# Adafruit_QT2040_Trinkey.net
KiCad netlist of a schematic drawn in EAGLE
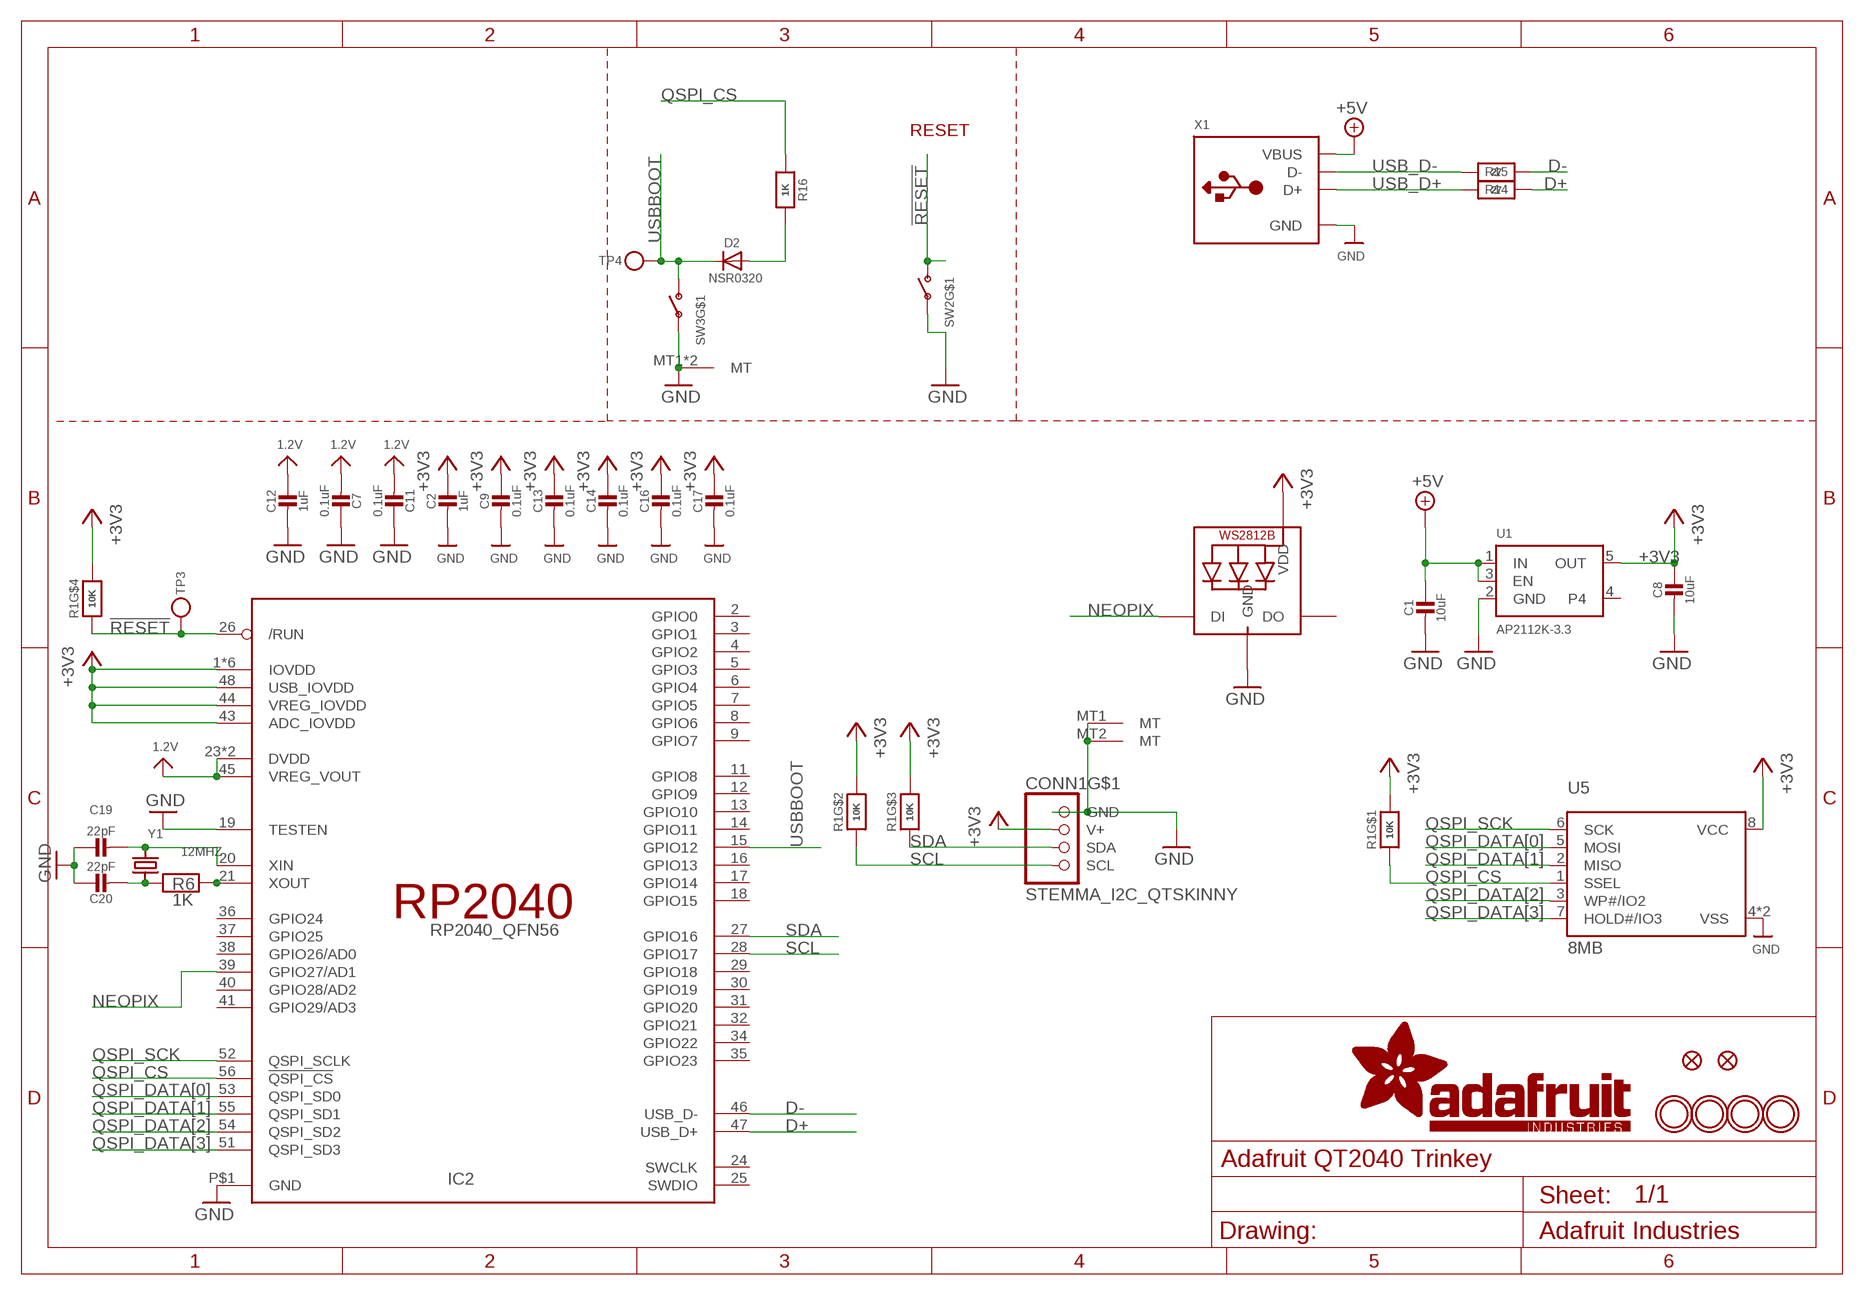
[diagram p0: schematic, sheet 1]

(export (version "E")
  (design (tool "Eeschema 10.0.6"))
  (components
    (comp (ref "C1")
      (value "10uF")
      (footprint "eagle-import:0805-NO")
      (libsource (lib "eagle-import") (part "CAP_CERAMIC0805-NOOUTLINE"))
    )
    (comp (ref "C2")
      (value "1uF")
      (footprint "eagle-import:0603-NO")
      (libsource (lib "eagle-import") (part "CAP_CERAMIC0603_NO"))
    )
    (comp (ref "C7")
      (value "0.1uF")
      (footprint "eagle-import:_0603MP")
      (libsource (lib "eagle-import") (part "CAP_CERAMIC_0603MP"))
    )
    (comp (ref "C8")
      (value "10uF")
      (footprint "eagle-import:0805-NO")
      (libsource (lib "eagle-import") (part "CAP_CERAMIC0805-NOOUTLINE"))
    )
    (comp (ref "C9")
      (value "0.1uF")
      (footprint "eagle-import:0603-NO")
      (libsource (lib "eagle-import") (part "CAP_CERAMIC0603_NO"))
    )
    (comp (ref "C11")
      (value "0.1uF")
      (footprint "eagle-import:0603-NO")
      (libsource (lib "eagle-import") (part "CAP_CERAMIC0603_NO"))
    )
    (comp (ref "C12")
      (value "1uF")
      (footprint "eagle-import:0603-NO")
      (libsource (lib "eagle-import") (part "CAP_CERAMIC0603_NO"))
    )
    (comp (ref "C13")
      (value "0.1uF")
      (footprint "eagle-import:0603-NO")
      (libsource (lib "eagle-import") (part "CAP_CERAMIC0603_NO"))
    )
    (comp (ref "C14")
      (value "0.1uF")
      (footprint "eagle-import:0603-NO")
      (libsource (lib "eagle-import") (part "CAP_CERAMIC0603_NO"))
    )
    (comp (ref "C16")
      (value "0.1uF")
      (footprint "eagle-import:0603-NO")
      (libsource (lib "eagle-import") (part "CAP_CERAMIC0603_NO"))
    )
    (comp (ref "C17")
      (value "0.1uF")
      (footprint "eagle-import:0603-NO")
      (libsource (lib "eagle-import") (part "CAP_CERAMIC0603_NO"))
    )
    (comp (ref "C19")
      (value "22pF")
      (footprint "eagle-import:0603-NO")
      (libsource (lib "eagle-import") (part "CAP_CERAMIC0603_NO"))
    )
    (comp (ref "C20")
      (value "22pF")
      (footprint "eagle-import:0603-NO")
      (libsource (lib "eagle-import") (part "CAP_CERAMIC0603_NO"))
    )
    (comp (ref "CONN1")
      (value "STEMMA_I2C_QTSKINNY")
      (footprint "eagle-import:JST_SH4_SKINNY")
      (libsource (lib "eagle-import") (part "STEMMA_I2C_QTSKINNY"))
    )
    (comp (ref "D2")
      (value "NSR0320")
      (footprint "eagle-import:SOD-323_MINI")
      (libsource (lib "eagle-import") (part "DIODE_SOD323MINI"))
    )
    (comp (ref "IC2")
      (value "RP2040_QFN56")
      (footprint "eagle-import:QFN56_7MM_REDUCEDEPAD")
      (libsource (lib "eagle-import") (part "RP2040_QFN56"))
    )
    (comp (ref "LED1")
      (value "WS2812B_SK6805_1515")
      (footprint "eagle-import:SK6805_1515")
      (libsource (lib "eagle-import") (part "WS2812B_SK6805_1515"))
    )
    (comp (ref "R1")
      (value "10K")
      (footprint "eagle-import:RESPACK_4X0603")
      (libsource (lib "eagle-import") (part "RESISTOR_4PACK"))
    )
    (comp (ref "R6")
      (value "1K")
      (footprint "eagle-import:0603-NO")
      (libsource (lib "eagle-import") (part "RESISTOR_0603_NOOUT"))
    )
    (comp (ref "R14")
      (value "27")
      (footprint "eagle-import:0603-NO")
      (libsource (lib "eagle-import") (part "RESISTOR_0603_NOOUT"))
    )
    (comp (ref "R15")
      (value "27")
      (footprint "eagle-import:0603-NO")
      (libsource (lib "eagle-import") (part "RESISTOR_0603_NOOUT"))
    )
    (comp (ref "R16")
      (value "1K")
      (footprint "eagle-import:0603-NO")
      (libsource (lib "eagle-import") (part "RESISTOR_0603_NOOUT"))
    )
    (comp (ref "SW2")
      (value "SWITCH_SPST_TACT_RA")
      (footprint "eagle-import:SPST_TACTILE_RA")
      (libsource (lib "eagle-import") (part "SWITCH_SPST_TACT_RA"))
    )
    (comp (ref "SW3")
      (value "SWITCH_SPST_TACT_RA")
      (footprint "eagle-import:SPST_TACTILE_RA")
      (libsource (lib "eagle-import") (part "SWITCH_SPST_TACT_RA"))
    )
    (comp (ref "TP3")
      (value "TESTPOINTROUND1.5MMNO")
      (footprint "eagle-import:TESTPOINT_ROUND_1.5MM_NO")
      (libsource (lib "eagle-import") (part "TESTPOINTROUND1.5MMNO"))
    )
    (comp (ref "TP4")
      (value "TESTPOINTROUND1.5MMNO")
      (footprint "eagle-import:TESTPOINT_ROUND_1.5MM_NO")
      (libsource (lib "eagle-import") (part "TESTPOINTROUND1.5MMNO"))
    )
    (comp (ref "U$1")
      (value "MOUNTINGHOLE2.5")
      (footprint "eagle-import:MOUNTINGHOLE_2.5_PLATED")
      (libsource (lib "eagle-import") (part "MOUNTINGHOLE2.5"))
    )
    (comp (ref "U$2")
      (value "MOUNTINGHOLE2.5")
      (footprint "eagle-import:MOUNTINGHOLE_2.5_PLATED")
      (libsource (lib "eagle-import") (part "MOUNTINGHOLE2.5"))
    )
    (comp (ref "U$4")
      (value "MOUNTINGHOLE2.5")
      (footprint "eagle-import:MOUNTINGHOLE_2.5_PLATED")
      (libsource (lib "eagle-import") (part "MOUNTINGHOLE2.5"))
    )
    (comp (ref "U$5")
      (value "MOUNTINGHOLE2.5")
      (footprint "eagle-import:MOUNTINGHOLE_2.5_PLATED")
      (libsource (lib "eagle-import") (part "MOUNTINGHOLE2.5"))
    )
    (comp (ref "U$6")
      (value "FIDUCIAL_1MM")
      (footprint "eagle-import:FIDUCIAL_1MM")
      (libsource (lib "eagle-import") (part "FIDUCIAL_1MM"))
    )
    (comp (ref "U$8")
      (value "FIDUCIAL_1MM")
      (footprint "eagle-import:FIDUCIAL_1MM")
      (libsource (lib "eagle-import") (part "FIDUCIAL_1MM"))
    )
    (comp (ref "U1")
      (value "AP2112K-3.3")
      (footprint "eagle-import:SOT23-5")
      (libsource (lib "eagle-import") (part "VREG_SOT23-5"))
    )
    (comp (ref "U5")
      (value "8MB")
      (footprint "eagle-import:USON8_4X4")
      (libsource (lib "eagle-import") (part "SPIFLASH_8PIN_4X4"))
    )
    (comp (ref "X1")
      (value "USB_TYPEAPCB")
      (footprint "eagle-import:USBA_PCB")
      (libsource (lib "eagle-import") (part "USB_TYPEAPCB"))
    )
    (comp (ref "Y1")
      (value "12MHZ")
      (footprint "eagle-import:CRYSTAL_2.5X2")
      (libsource (lib "eagle-import") (part "CRYSTAL2.5X2.0"))
    )
  )
  (nets
    (net (code "1") (name "+3V3") (class "Default")
      (node (ref "C13") (pin "1") (pinfunction "1_1") (pintype "passive"))
      (node (ref "C14") (pin "1") (pinfunction "1_1") (pintype "passive"))
      (node (ref "C16") (pin "1") (pinfunction "1_1") (pintype "passive"))
      (node (ref "C17") (pin "1") (pinfunction "1_1") (pintype "passive"))
      (node (ref "C2") (pin "1") (pinfunction "1_1") (pintype "passive"))
      (node (ref "C8") (pin "1") (pinfunction "1_1") (pintype "passive"))
      (node (ref "C9") (pin "1") (pinfunction "1_1") (pintype "passive"))
      (node (ref "CONN1") (pin "2") (pinfunction "V+_2") (pintype "passive"))
      (node (ref "IC2") (pin "1") (pinfunction "IOVDD_1") (pintype "power_in"))
      (node (ref "IC2") (pin "10") (pinfunction "IOVDD_10") (pintype "power_in"))
      (node (ref "IC2") (pin "22") (pinfunction "IOVDD_22") (pintype "power_in"))
      (node (ref "IC2") (pin "33") (pinfunction "IOVDD_33") (pintype "power_in"))
      (node (ref "IC2") (pin "42") (pinfunction "IOVDD_42") (pintype "power_in"))
      (node (ref "IC2") (pin "43") (pinfunction "ADC_IOVDD_43") (pintype "power_in"))
      (node (ref "IC2") (pin "44") (pinfunction "VREG_IOVDD_44") (pintype "power_in"))
      (node (ref "IC2") (pin "48") (pinfunction "USB_IOVDD_48") (pintype "power_in"))
      (node (ref "IC2") (pin "49") (pinfunction "IOVDD_49") (pintype "power_in"))
      (node (ref "LED1") (pin "2") (pinfunction "VDD_2") (pintype "power_in"))
      (node (ref "R1") (pin "5") (pinfunction "2_5") (pintype "passive"))
      (node (ref "R1") (pin "6") (pinfunction "2_6") (pintype "passive"))
      (node (ref "R1") (pin "7") (pinfunction "2_7") (pintype "passive"))
      (node (ref "R1") (pin "8") (pinfunction "2_8") (pintype "passive"))
      (node (ref "U1") (pin "5") (pinfunction "OUT_5") (pintype "power_in"))
      (node (ref "U5") (pin "8") (pinfunction "VCC_8") (pintype "bidirectional"))
    )
    (net (code "2") (name "+5V") (class "Default")
      (node (ref "C1") (pin "1") (pinfunction "1_1") (pintype "passive"))
      (node (ref "U1") (pin "1") (pinfunction "IN_1") (pintype "power_in"))
      (node (ref "U1") (pin "3") (pinfunction "EN_3") (pintype "input"))
      (node (ref "X1") (pin "VCC") (pinfunction "VBUS_VCC") (pintype "power_in"))
    )
    (net (code "3") (name "/D+") (class "Default")
      (node (ref "IC2") (pin "47") (pinfunction "USB_D+_47") (pintype "bidirectional"))
      (node (ref "R15") (pin "2") (pinfunction "2_2") (pintype "passive"))
    )
    (net (code "4") (name "/D-") (class "Default")
      (node (ref "IC2") (pin "46") (pinfunction "USB_D-_46") (pintype "bidirectional"))
      (node (ref "R14") (pin "2") (pinfunction "2_2") (pintype "passive"))
    )
    (net (code "5") (name "/NEOPIX") (class "Default")
      (node (ref "IC2") (pin "39") (pinfunction "GPIO27/AD1_39") (pintype "bidirectional"))
      (node (ref "LED1") (pin "1") (pinfunction "DI_1") (pintype "input"))
    )
    (net (code "6") (name "/QSPI_CS") (class "Default")
      (node (ref "IC2") (pin "56") (pinfunction "~{QSPI_CS}_56") (pintype "bidirectional"))
      (node (ref "R1") (pin "1") (pinfunction "1_1") (pintype "passive"))
      (node (ref "R16") (pin "1") (pinfunction "1_1") (pintype "passive"))
      (node (ref "U5") (pin "1") (pinfunction "SSEL_1") (pintype "bidirectional"))
    )
    (net (code "7") (name "/QSPI_DATA[0]") (class "Default")
      (node (ref "IC2") (pin "53") (pinfunction "QSPI_SD0_53") (pintype "bidirectional"))
      (node (ref "U5") (pin "5") (pinfunction "MOSI_5") (pintype "bidirectional"))
    )
    (net (code "8") (name "/QSPI_DATA[1]") (class "Default")
      (node (ref "IC2") (pin "55") (pinfunction "QSPI_SD1_55") (pintype "bidirectional"))
      (node (ref "U5") (pin "2") (pinfunction "MISO_2") (pintype "bidirectional"))
    )
    (net (code "9") (name "/QSPI_DATA[2]") (class "Default")
      (node (ref "IC2") (pin "54") (pinfunction "QSPI_SD2_54") (pintype "bidirectional"))
      (node (ref "U5") (pin "3") (pinfunction "WP#/IO2_3") (pintype "bidirectional"))
    )
    (net (code "10") (name "/QSPI_DATA[3]") (class "Default")
      (node (ref "IC2") (pin "51") (pinfunction "QSPI_SD3_51") (pintype "bidirectional"))
      (node (ref "U5") (pin "7") (pinfunction "HOLD#/IO3_7") (pintype "bidirectional"))
    )
    (net (code "11") (name "/QSPI_SCK") (class "Default")
      (node (ref "IC2") (pin "52") (pinfunction "QSPI_SCLK_52") (pintype "bidirectional"))
      (node (ref "U5") (pin "6") (pinfunction "SCK_6") (pintype "bidirectional"))
    )
    (net (code "12") (name "/SCL") (class "Default")
      (node (ref "CONN1") (pin "4") (pinfunction "SCL_4") (pintype "passive"))
      (node (ref "IC2") (pin "28") (pinfunction "GPIO17_28") (pintype "bidirectional"))
      (node (ref "R1") (pin "2") (pinfunction "1_2") (pintype "passive"))
    )
    (net (code "13") (name "/SDA") (class "Default")
      (node (ref "CONN1") (pin "3") (pinfunction "SDA_3") (pintype "passive"))
      (node (ref "IC2") (pin "27") (pinfunction "GPIO16_27") (pintype "bidirectional"))
      (node (ref "R1") (pin "3") (pinfunction "1_3") (pintype "passive"))
    )
    (net (code "14") (name "/USBBOOT") (class "Default")
      (node (ref "D2") (pin "C") (pinfunction "C_C") (pintype "passive"))
      (node (ref "IC2") (pin "15") (pinfunction "GPIO12_15") (pintype "bidirectional"))
      (node (ref "SW3") (pin "2") (pinfunction "S_2") (pintype "passive"))
      (node (ref "TP4") (pin "P$1") (pinfunction "P$1_P$1") (pintype "bidirectional"))
    )
    (net (code "15") (name "/USB_D+") (class "Default")
      (node (ref "R15") (pin "1") (pinfunction "1_1") (pintype "passive"))
      (node (ref "X1") (pin "USB_PLUS") (pinfunction "D+_USB_PLUS") (pintype "bidirectional"))
    )
    (net (code "16") (name "/USB_D-") (class "Default")
      (node (ref "R14") (pin "1") (pinfunction "1_1") (pintype "passive"))
      (node (ref "X1") (pin "USB_NEG") (pinfunction "D-_USB_NEG") (pintype "bidirectional"))
    )
    (net (code "17") (name "/~{RESET}") (class "Default")
      (node (ref "IC2") (pin "26") (pinfunction "/RUN_26") (pintype "bidirectional"))
      (node (ref "R1") (pin "4") (pinfunction "1_4") (pintype "passive"))
      (node (ref "SW2") (pin "2") (pinfunction "S_2") (pintype "passive"))
      (node (ref "TP3") (pin "P$1") (pinfunction "P$1_P$1") (pintype "bidirectional"))
    )
    (net (code "18") (name "1.2V") (class "Default")
      (node (ref "C11") (pin "2") (pinfunction "2_2") (pintype "passive"))
      (node (ref "C12") (pin "1") (pinfunction "1_1") (pintype "passive"))
      (node (ref "C7") (pin "2") (pinfunction "2_2") (pintype "passive"))
      (node (ref "IC2") (pin "23") (pinfunction "DVDD_23") (pintype "power_in"))
      (node (ref "IC2") (pin "45") (pinfunction "VREG_VOUT_45") (pintype "power_in"))
      (node (ref "IC2") (pin "50") (pinfunction "DVDD_50") (pintype "power_in"))
    )
    (net (code "19") (name "GND") (class "Default")
      (node (ref "C1") (pin "2") (pinfunction "2_2") (pintype "passive"))
      (node (ref "C11") (pin "1") (pinfunction "1_1") (pintype "passive"))
      (node (ref "C12") (pin "2") (pinfunction "2_2") (pintype "passive"))
      (node (ref "C13") (pin "2") (pinfunction "2_2") (pintype "passive"))
      (node (ref "C14") (pin "2") (pinfunction "2_2") (pintype "passive"))
      (node (ref "C16") (pin "2") (pinfunction "2_2") (pintype "passive"))
      (node (ref "C17") (pin "2") (pinfunction "2_2") (pintype "passive"))
      (node (ref "C19") (pin "1") (pinfunction "1_1") (pintype "passive"))
      (node (ref "C2") (pin "2") (pinfunction "2_2") (pintype "passive"))
      (node (ref "C20") (pin "1") (pinfunction "1_1") (pintype "passive"))
      (node (ref "C7") (pin "1") (pinfunction "1_1") (pintype "passive"))
      (node (ref "C8") (pin "2") (pinfunction "2_2") (pintype "passive"))
      (node (ref "C9") (pin "2") (pinfunction "2_2") (pintype "passive"))
      (node (ref "CONN1") (pin "1") (pinfunction "GND_1") (pintype "passive"))
      (node (ref "CONN1") (pin "MT1") (pinfunction "MT_MT1") (pintype "bidirectional"))
      (node (ref "CONN1") (pin "MT2") (pinfunction "MT_MT2") (pintype "bidirectional"))
      (node (ref "IC2") (pin "19") (pinfunction "TESTEN_19") (pintype "input"))
      (node (ref "IC2") (pin "P$1") (pinfunction "GND_P$1") (pintype "power_in"))
      (node (ref "LED1") (pin "4") (pinfunction "GND_4") (pintype "power_in"))
      (node (ref "SW2") (pin "1") (pinfunction "P_1") (pintype "passive"))
      (node (ref "SW3") (pin "1") (pinfunction "P_1") (pintype "passive"))
      (node (ref "SW3") (pin "MT1") (pinfunction "MT_MT1") (pintype "bidirectional"))
      (node (ref "SW3") (pin "MT2") (pinfunction "MT_MT2") (pintype "bidirectional"))
      (node (ref "U1") (pin "2") (pinfunction "GND_2") (pintype "power_in"))
      (node (ref "U5") (pin "4") (pinfunction "VSS_4") (pintype "bidirectional"))
      (node (ref "U5") (pin "PAD") (pinfunction "VSS_PAD") (pintype "bidirectional"))
      (node (ref "X1") (pin "GND") (pinfunction "GND_GND") (pintype "power_in"))
    )
    (net (code "20") (name "Net-(C20-Pad2)") (class "Default")
      (node (ref "C20") (pin "2") (pinfunction "2_2") (pintype "passive"))
      (node (ref "R6") (pin "1") (pinfunction "1_1") (pintype "passive"))
      (node (ref "Y1") (pin "1") (pinfunction "1_1") (pintype "passive"))
    )
    (net (code "21") (name "Net-(D2-PadA)") (class "Default")
      (node (ref "D2") (pin "A") (pinfunction "A_A") (pintype "passive"))
      (node (ref "R16") (pin "2") (pinfunction "2_2") (pintype "passive"))
    )
    (net (code "22") (name "Net-(IC2-XIN)") (class "Default")
      (node (ref "C19") (pin "2") (pinfunction "2_2") (pintype "passive"))
      (node (ref "IC2") (pin "20") (pinfunction "XIN_20") (pintype "input"))
      (node (ref "Y1") (pin "3") (pinfunction "2_3") (pintype "passive"))
    )
    (net (code "23") (name "Net-(IC2-XOUT)") (class "Default")
      (node (ref "IC2") (pin "21") (pinfunction "XOUT_21") (pintype "output"))
      (node (ref "R6") (pin "2") (pinfunction "2_2") (pintype "passive"))
    )
    (net (code "24") (name "unconnected-(IC2-GPIO0-Pad2)") (class "Default")
      (node (ref "IC2") (pin "2") (pinfunction "GPIO0_2") (pintype "bidirectional"))
    )
    (net (code "25") (name "unconnected-(IC2-GPIO1-Pad3)") (class "Default")
      (node (ref "IC2") (pin "3") (pinfunction "GPIO1_3") (pintype "bidirectional"))
    )
    (net (code "26") (name "unconnected-(IC2-GPIO2-Pad4)") (class "Default")
      (node (ref "IC2") (pin "4") (pinfunction "GPIO2_4") (pintype "bidirectional"))
    )
    (net (code "27") (name "unconnected-(IC2-GPIO3-Pad5)") (class "Default")
      (node (ref "IC2") (pin "5") (pinfunction "GPIO3_5") (pintype "bidirectional"))
    )
    (net (code "28") (name "unconnected-(IC2-GPIO4-Pad6)") (class "Default")
      (node (ref "IC2") (pin "6") (pinfunction "GPIO4_6") (pintype "bidirectional"))
    )
    (net (code "29") (name "unconnected-(IC2-GPIO5-Pad7)") (class "Default")
      (node (ref "IC2") (pin "7") (pinfunction "GPIO5_7") (pintype "bidirectional"))
    )
    (net (code "30") (name "unconnected-(IC2-GPIO6-Pad8)") (class "Default")
      (node (ref "IC2") (pin "8") (pinfunction "GPIO6_8") (pintype "bidirectional"))
    )
    (net (code "31") (name "unconnected-(IC2-GPIO7-Pad9)") (class "Default")
      (node (ref "IC2") (pin "9") (pinfunction "GPIO7_9") (pintype "bidirectional"))
    )
    (net (code "32") (name "unconnected-(IC2-GPIO8-Pad11)") (class "Default")
      (node (ref "IC2") (pin "11") (pinfunction "GPIO8_11") (pintype "bidirectional"))
    )
    (net (code "33") (name "unconnected-(IC2-GPIO9-Pad12)") (class "Default")
      (node (ref "IC2") (pin "12") (pinfunction "GPIO9_12") (pintype "bidirectional"))
    )
    (net (code "34") (name "unconnected-(IC2-GPIO10-Pad13)") (class "Default")
      (node (ref "IC2") (pin "13") (pinfunction "GPIO10_13") (pintype "bidirectional"))
    )
    (net (code "35") (name "unconnected-(IC2-GPIO11-Pad14)") (class "Default")
      (node (ref "IC2") (pin "14") (pinfunction "GPIO11_14") (pintype "bidirectional"))
    )
    (net (code "36") (name "unconnected-(IC2-GPIO13-Pad16)") (class "Default")
      (node (ref "IC2") (pin "16") (pinfunction "GPIO13_16") (pintype "bidirectional"))
    )
    (net (code "37") (name "unconnected-(IC2-GPIO14-Pad17)") (class "Default")
      (node (ref "IC2") (pin "17") (pinfunction "GPIO14_17") (pintype "bidirectional"))
    )
    (net (code "38") (name "unconnected-(IC2-GPIO15-Pad18)") (class "Default")
      (node (ref "IC2") (pin "18") (pinfunction "GPIO15_18") (pintype "bidirectional"))
    )
    (net (code "39") (name "unconnected-(IC2-GPIO18-Pad29)") (class "Default")
      (node (ref "IC2") (pin "29") (pinfunction "GPIO18_29") (pintype "bidirectional"))
    )
    (net (code "40") (name "unconnected-(IC2-GPIO19-Pad30)") (class "Default")
      (node (ref "IC2") (pin "30") (pinfunction "GPIO19_30") (pintype "bidirectional"))
    )
    (net (code "41") (name "unconnected-(IC2-GPIO20-Pad31)") (class "Default")
      (node (ref "IC2") (pin "31") (pinfunction "GPIO20_31") (pintype "bidirectional"))
    )
    (net (code "42") (name "unconnected-(IC2-GPIO21-Pad32)") (class "Default")
      (node (ref "IC2") (pin "32") (pinfunction "GPIO21_32") (pintype "bidirectional"))
    )
    (net (code "43") (name "unconnected-(IC2-GPIO22-Pad34)") (class "Default")
      (node (ref "IC2") (pin "34") (pinfunction "GPIO22_34") (pintype "bidirectional"))
    )
    (net (code "44") (name "unconnected-(IC2-GPIO23-Pad35)") (class "Default")
      (node (ref "IC2") (pin "35") (pinfunction "GPIO23_35") (pintype "bidirectional"))
    )
    (net (code "45") (name "unconnected-(IC2-GPIO24-Pad36)") (class "Default")
      (node (ref "IC2") (pin "36") (pinfunction "GPIO24_36") (pintype "bidirectional"))
    )
    (net (code "46") (name "unconnected-(IC2-GPIO25-Pad37)") (class "Default")
      (node (ref "IC2") (pin "37") (pinfunction "GPIO25_37") (pintype "bidirectional"))
    )
    (net (code "47") (name "unconnected-(IC2-GPIO26{slash}AD0-Pad38)") (class "Default")
      (node (ref "IC2") (pin "38") (pinfunction "GPIO26/AD0_38") (pintype "bidirectional"))
    )
    (net (code "48") (name "unconnected-(IC2-GPIO28{slash}AD2-Pad40)") (class "Default")
      (node (ref "IC2") (pin "40") (pinfunction "GPIO28/AD2_40") (pintype "bidirectional"))
    )
    (net (code "49") (name "unconnected-(IC2-GPIO29{slash}AD3-Pad41)") (class "Default")
      (node (ref "IC2") (pin "41") (pinfunction "GPIO29/AD3_41") (pintype "bidirectional"))
    )
    (net (code "50") (name "unconnected-(IC2-SWCLK-Pad24)") (class "Default")
      (node (ref "IC2") (pin "24") (pinfunction "SWCLK_24") (pintype "bidirectional"))
    )
    (net (code "51") (name "unconnected-(IC2-SWDIO-Pad25)") (class "Default")
      (node (ref "IC2") (pin "25") (pinfunction "SWDIO_25") (pintype "bidirectional"))
    )
    (net (code "52") (name "unconnected-(LED1-DO-Pad3)") (class "Default")
      (node (ref "LED1") (pin "3") (pinfunction "DO_3") (pintype "output"))
    )
    (net (code "53") (name "unconnected-(U1-P4-Pad4)") (class "Default")
      (node (ref "U1") (pin "4") (pinfunction "P4_4") (pintype "bidirectional"))
    )
  )
)
